# CAN.net
KiCad netlist of a schematic drawn in Altium Designer
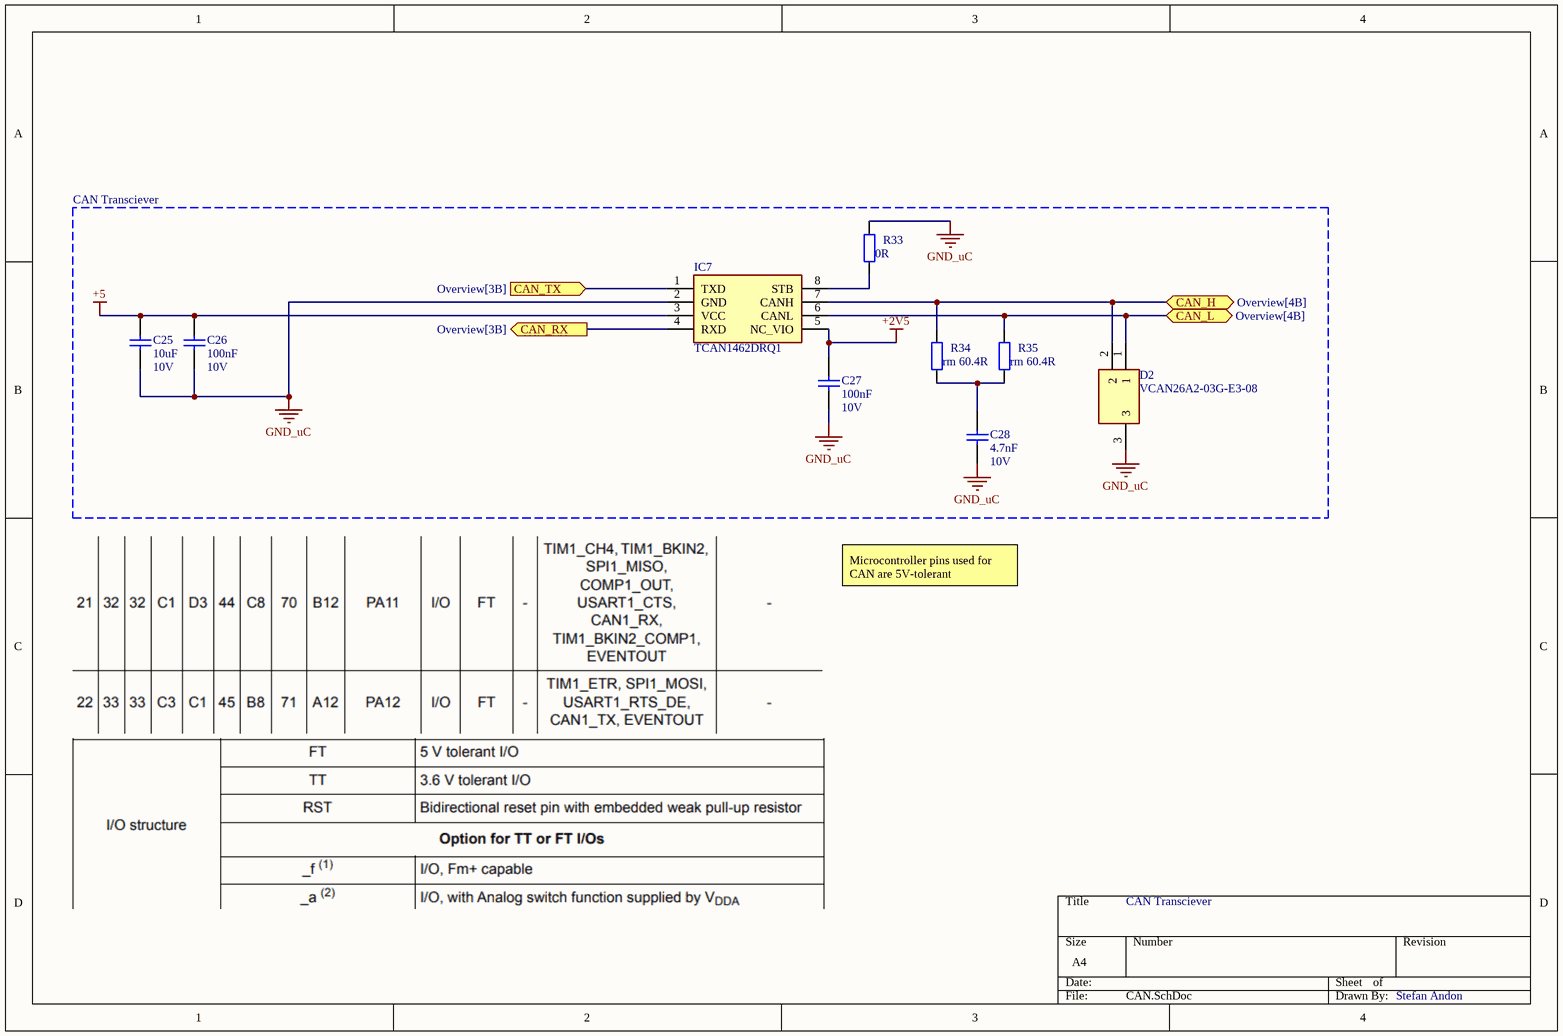
[diagram p0: CAN.SchDoc]

(export (version "E")
  (design (tool "Eeschema 10.0.6"))
  (components
    (comp (ref "C25")
      (value "10uF")
      (footprint "CAP_0603")
      (description "SMD Capacitor")
      (fields
        (field (name "TOLERANCE") "tbd")
        (field (name "VOLTAGE") "10V")
        (field (name "Comment") "Capacitor_SMD")
      )
      (libsource (lib "TUfast e") (part "SMD Capacitor"))
    )
    (comp (ref "C26")
      (value "100nF")
      (footprint "CAP_0603")
      (description "SMD Capacitor")
      (fields
        (field (name "TOLERANCE") "tbd")
        (field (name "VOLTAGE") "10V")
        (field (name "Comment") "Capacitor_SMD")
      )
      (libsource (lib "TUfast e") (part "SMD Capacitor"))
    )
    (comp (ref "C27")
      (value "100nF")
      (footprint "CAP_0603")
      (description "SMD Capacitor")
      (fields
        (field (name "TOLERANCE") "tbd")
        (field (name "VOLTAGE") "10V")
        (field (name "Comment") "Capacitor_SMD")
      )
      (libsource (lib "TUfast e") (part "SMD Capacitor"))
    )
    (comp (ref "C28")
      (value "4.7nF")
      (footprint "CAP_0603")
      (description "SMD Capacitor")
      (fields
        (field (name "TOLERANCE") "tbd")
        (field (name "VOLTAGE") "10V")
        (field (name "Comment") "Capacitor_SMD")
      )
      (libsource (lib "TUfast e") (part "SMD Capacitor"))
    )
    (comp (ref "D2")
      (value "VCAN26A2-03G-E3-08")
      (footprint "SamacSys:SOT65P230X110-3N")
      (description "TVS Diode (Bi-directional)")
      (fields (field (name "MOUSER PART NUMBER") "78-VCAN26A2-03G-E308"))
      (libsource (lib "*") (part "VCAN26A2-03G-E3-08"))
    )
    (comp (ref "IC7")
      (value "TCAN1462DRQ1")
      (footprint "SamacSys:SOIC127P600X175-8N")
      (description "Integrated Circuit")
      (fields (field (name "MOUSER PART NUMBER") "595-TCAN1462DRQ1"))
      (libsource (lib "*") (part "TCAN1462DRQ1"))
    )
    (comp (ref "R33")
      (value "0R")
      (footprint "RES_0603")
      (fields
        (field (name "TOLERANCE") "tbd")
        (field (name "POWER") "7W")
        (field (name "Comment") "Resistor_SMD")
      )
      (libsource (lib "TUfast e") (part "Resistor"))
    )
    (comp (ref "R34")
      (value "rm 60.4R")
      (footprint "RES_0603")
      (fields
        (field (name "TOLERANCE") "tbd")
        (field (name "POWER") "7W")
        (field (name "Comment") "Resistor_SMD")
      )
      (libsource (lib "TUfast e") (part "Resistor"))
    )
    (comp (ref "R35")
      (value "rm 60.4R")
      (footprint "RES_0603")
      (fields
        (field (name "TOLERANCE") "tbd")
        (field (name "POWER") "7W")
        (field (name "Comment") "Resistor_SMD")
      )
      (libsource (lib "TUfast e") (part "Resistor"))
    )
  )
  (nets
    (net (code "1") (name "+2V5") (class "Default")
      (node (ref "C27") (pin "1") (pinfunction "1_1") (pintype "passive"))
      (node (ref "IC7") (pin "5") (pinfunction "NC_VIO_5") (pintype "passive"))
    )
    (net (code "2") (name "+5") (class "Default")
      (node (ref "C25") (pin "1") (pinfunction "1_1") (pintype "passive"))
      (node (ref "C26") (pin "1") (pinfunction "1_1") (pintype "passive"))
      (node (ref "IC7") (pin "3") (pinfunction "VCC_3") (pintype "passive"))
    )
    (net (code "3") (name "/CAN_H") (class "Default")
      (node (ref "D2") (pin "2") (pinfunction "2_2") (pintype "passive"))
      (node (ref "IC7") (pin "7") (pinfunction "CANH_7") (pintype "passive"))
      (node (ref "R34") (pin "1") (pinfunction "1_1") (pintype "passive"))
    )
    (net (code "4") (name "/CAN_L") (class "Default")
      (node (ref "D2") (pin "1") (pinfunction "1_1") (pintype "passive"))
      (node (ref "IC7") (pin "6") (pinfunction "CANL_6") (pintype "passive"))
      (node (ref "R35") (pin "1") (pinfunction "1_1") (pintype "passive"))
    )
    (net (code "5") (name "/CAN_RX") (class "Default")
      (node (ref "IC7") (pin "4") (pinfunction "RXD_4") (pintype "passive"))
    )
    (net (code "6") (name "/CAN_TX") (class "Default")
      (node (ref "IC7") (pin "1") (pinfunction "TXD_1") (pintype "passive"))
    )
    (net (code "7") (name "GND_uC") (class "Default")
      (node (ref "C25") (pin "2") (pinfunction "2_2") (pintype "passive"))
      (node (ref "C26") (pin "2") (pinfunction "2_2") (pintype "passive"))
      (node (ref "C27") (pin "2") (pinfunction "2_2") (pintype "passive"))
      (node (ref "C28") (pin "2") (pinfunction "2_2") (pintype "passive"))
      (node (ref "D2") (pin "3") (pinfunction "3_3") (pintype "passive"))
      (node (ref "IC7") (pin "2") (pinfunction "GND_2") (pintype "passive"))
      (node (ref "R33") (pin "1") (pinfunction "1_1") (pintype "passive"))
    )
    (net (code "8") (name "Net-(C28-Pad1)") (class "Default")
      (node (ref "C28") (pin "1") (pinfunction "1_1") (pintype "passive"))
      (node (ref "R34") (pin "2") (pinfunction "2_2") (pintype "passive"))
      (node (ref "R35") (pin "2") (pinfunction "2_2") (pintype "passive"))
    )
    (net (code "9") (name "Net-(IC7-STB)") (class "Default")
      (node (ref "IC7") (pin "8") (pinfunction "STB_8") (pintype "passive"))
      (node (ref "R33") (pin "2") (pinfunction "2_2") (pintype "passive"))
    )
  )
)
